# MagSwitch.net
KiCad netlist of a schematic drawn in EAGLE
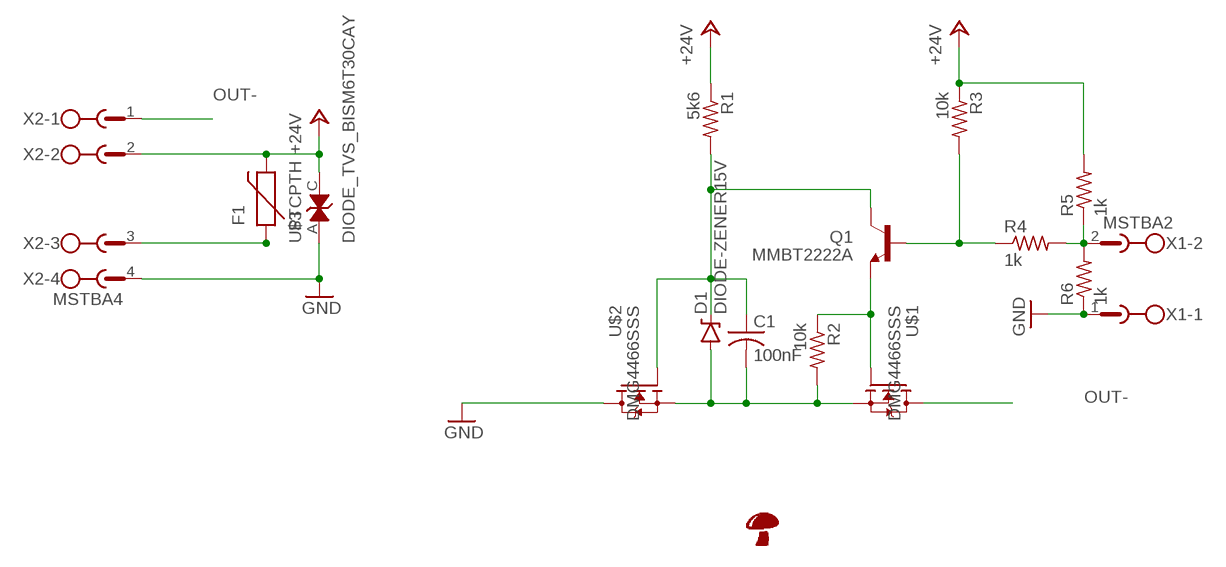
[diagram p0: schematic, sheet 1]

(export (version "E")
  (design (tool "Eeschema 10.0.6"))
  (components
    (comp (ref "C1")
      (value "100nF")
      (footprint "eagle-import:C0805")
      (libsource (lib "eagle-import") (part "C-USC0805"))
    )
    (comp (ref "D1")
      (value "DIODE-ZENER15V")
      (footprint "eagle-import:SOD-323")
      (libsource (lib "eagle-import") (part "DIODE-ZENER15V"))
    )
    (comp (ref "F1")
      (value "PTCPTH")
      (footprint "eagle-import:PTC")
      (libsource (lib "eagle-import") (part "PTCPTH"))
    )
    (comp (ref "Q1")
      (value "MMBT2222A")
      (footprint "eagle-import:SOT23-3")
      (libsource (lib "eagle-import") (part "TRANSISTOR_NPNMMBT2222A"))
    )
    (comp (ref "R1")
      (value "5k6")
      (footprint "eagle-import:M0805")
      (libsource (lib "eagle-import") (part "R-US_M0805"))
    )
    (comp (ref "R2")
      (value "10k")
      (footprint "eagle-import:M0805")
      (libsource (lib "eagle-import") (part "R-US_M0805"))
    )
    (comp (ref "R3")
      (value "10k")
      (footprint "eagle-import:M0805")
      (libsource (lib "eagle-import") (part "R-US_M0805"))
    )
    (comp (ref "R4")
      (value "1k")
      (footprint "eagle-import:M0805")
      (libsource (lib "eagle-import") (part "R-US_M0805"))
    )
    (comp (ref "R5")
      (value "1k")
      (footprint "eagle-import:M0805")
      (libsource (lib "eagle-import") (part "R-US_M0805"))
    )
    (comp (ref "R6")
      (value "1k")
      (footprint "eagle-import:M0805")
      (libsource (lib "eagle-import") (part "R-US_M0805"))
    )
    (comp (ref "U$1")
      (value "DMG4466SSS")
      (footprint "eagle-import:SO08")
      (libsource (lib "eagle-import") (part "DMG4466SSS"))
    )
    (comp (ref "U$2")
      (value "DMG4466SSS")
      (footprint "eagle-import:SO08")
      (libsource (lib "eagle-import") (part "DMG4466SSS"))
    )
    (comp (ref "U$3")
      (value "DIODE_TVS_BISM6T30CAY")
      (footprint "eagle-import:SMB-DIODE")
      (libsource (lib "eagle-import") (part "DIODE_TVS_BISM6T30CAY"))
    )
    (comp (ref "U$4")
      (value "SHROOM5MM")
      (footprint "eagle-import:SHROOM")
      (libsource (lib "eagle-import") (part "SHROOM5MM"))
    )
    (comp (ref "X1")
      (value "MSTBA2")
      (footprint "eagle-import:MSTBA2")
      (fields (field (name "MF") "FARNELL") (field (name "MPN") "1757242"))
      (libsource (lib "eagle-import") (part "MSTBA2"))
    )
    (comp (ref "X2")
      (value "MSTBA4")
      (footprint "eagle-import:MSTBA4")
      (fields (field (name "MF") "FARNELL") (field (name "MPN") "1757268"))
      (libsource (lib "eagle-import") (part "MSTBA4"))
    )
  )
  (nets
    (net (code "1") (name "+24V") (class "Default")
      (node (ref "F1") (pin "P$2") (pinfunction "2_P$2") (pintype "bidirectional"))
      (node (ref "R1") (pin "1") (pinfunction "1_1") (pintype "passive"))
      (node (ref "R3") (pin "1") (pinfunction "1_1") (pintype "passive"))
      (node (ref "R5") (pin "2") (pinfunction "2_2") (pintype "passive"))
      (node (ref "U$3") (pin "C") (pinfunction "P$2_C") (pintype "bidirectional"))
      (node (ref "X2") (pin "2") (pinfunction "1_2") (pintype "passive"))
    )
    (net (code "2") (name "/OUT-") (class "Default")
      (node (ref "U$1") (pin "5") (pinfunction "D_5") (pintype "passive"))
      (node (ref "U$1") (pin "6") (pinfunction "D_6") (pintype "passive"))
      (node (ref "U$1") (pin "7") (pinfunction "D_7") (pintype "passive"))
      (node (ref "U$1") (pin "8") (pinfunction "D_8") (pintype "passive"))
      (node (ref "X2") (pin "1") (pinfunction "1_1") (pintype "passive"))
    )
    (net (code "3") (name "GND") (class "Default")
      (node (ref "R6") (pin "1") (pinfunction "1_1") (pintype "passive"))
      (node (ref "U$2") (pin "5") (pinfunction "D_5") (pintype "passive"))
      (node (ref "U$2") (pin "6") (pinfunction "D_6") (pintype "passive"))
      (node (ref "U$2") (pin "7") (pinfunction "D_7") (pintype "passive"))
      (node (ref "U$2") (pin "8") (pinfunction "D_8") (pintype "passive"))
      (node (ref "U$3") (pin "A") (pinfunction "P$1_A") (pintype "bidirectional"))
      (node (ref "X1") (pin "1") (pinfunction "1_1") (pintype "passive"))
      (node (ref "X2") (pin "4") (pinfunction "1_4") (pintype "passive"))
    )
    (net (code "4") (name "Net-(C1-Pad2)") (class "Default")
      (node (ref "C1") (pin "2") (pinfunction "2_2") (pintype "passive"))
      (node (ref "D1") (pin "A") (pinfunction "A_A") (pintype "passive"))
      (node (ref "R2") (pin "2") (pinfunction "2_2") (pintype "passive"))
      (node (ref "U$1") (pin "1") (pinfunction "S_1") (pintype "passive"))
      (node (ref "U$1") (pin "2") (pinfunction "S_2") (pintype "passive"))
      (node (ref "U$1") (pin "3") (pinfunction "S_3") (pintype "passive"))
      (node (ref "U$2") (pin "1") (pinfunction "S_1") (pintype "passive"))
      (node (ref "U$2") (pin "2") (pinfunction "S_2") (pintype "passive"))
      (node (ref "U$2") (pin "3") (pinfunction "S_3") (pintype "passive"))
    )
    (net (code "5") (name "Net-(F1-1)") (class "Default")
      (node (ref "F1") (pin "P$1") (pinfunction "1_P$1") (pintype "bidirectional"))
      (node (ref "X2") (pin "3") (pinfunction "1_3") (pintype "passive"))
    )
    (net (code "6") (name "Net-(Q1-B)") (class "Default")
      (node (ref "Q1") (pin "1") (pinfunction "B_1") (pintype "passive"))
      (node (ref "R3") (pin "2") (pinfunction "2_2") (pintype "passive"))
      (node (ref "R4") (pin "1") (pinfunction "1_1") (pintype "passive"))
    )
    (net (code "7") (name "Net-(Q1-C)") (class "Default")
      (node (ref "C1") (pin "1") (pinfunction "1_1") (pintype "passive"))
      (node (ref "D1") (pin "C") (pinfunction "C_C") (pintype "passive"))
      (node (ref "Q1") (pin "3") (pinfunction "C_3") (pintype "passive"))
      (node (ref "R1") (pin "2") (pinfunction "2_2") (pintype "passive"))
      (node (ref "U$2") (pin "4") (pinfunction "G_4") (pintype "passive"))
    )
    (net (code "8") (name "Net-(Q1-E)") (class "Default")
      (node (ref "Q1") (pin "2") (pinfunction "E_2") (pintype "passive"))
      (node (ref "R2") (pin "1") (pinfunction "1_1") (pintype "passive"))
      (node (ref "U$1") (pin "4") (pinfunction "G_4") (pintype "passive"))
    )
    (net (code "9") (name "Net-(X1B-1)") (class "Default")
      (node (ref "R4") (pin "2") (pinfunction "2_2") (pintype "passive"))
      (node (ref "R5") (pin "1") (pinfunction "1_1") (pintype "passive"))
      (node (ref "R6") (pin "2") (pinfunction "2_2") (pintype "passive"))
      (node (ref "X1") (pin "2") (pinfunction "1_2") (pintype "passive"))
    )
  )
)
